# BT_AQ_DOL_R5.net
KiCad netlist of a schematic drawn in EAGLE
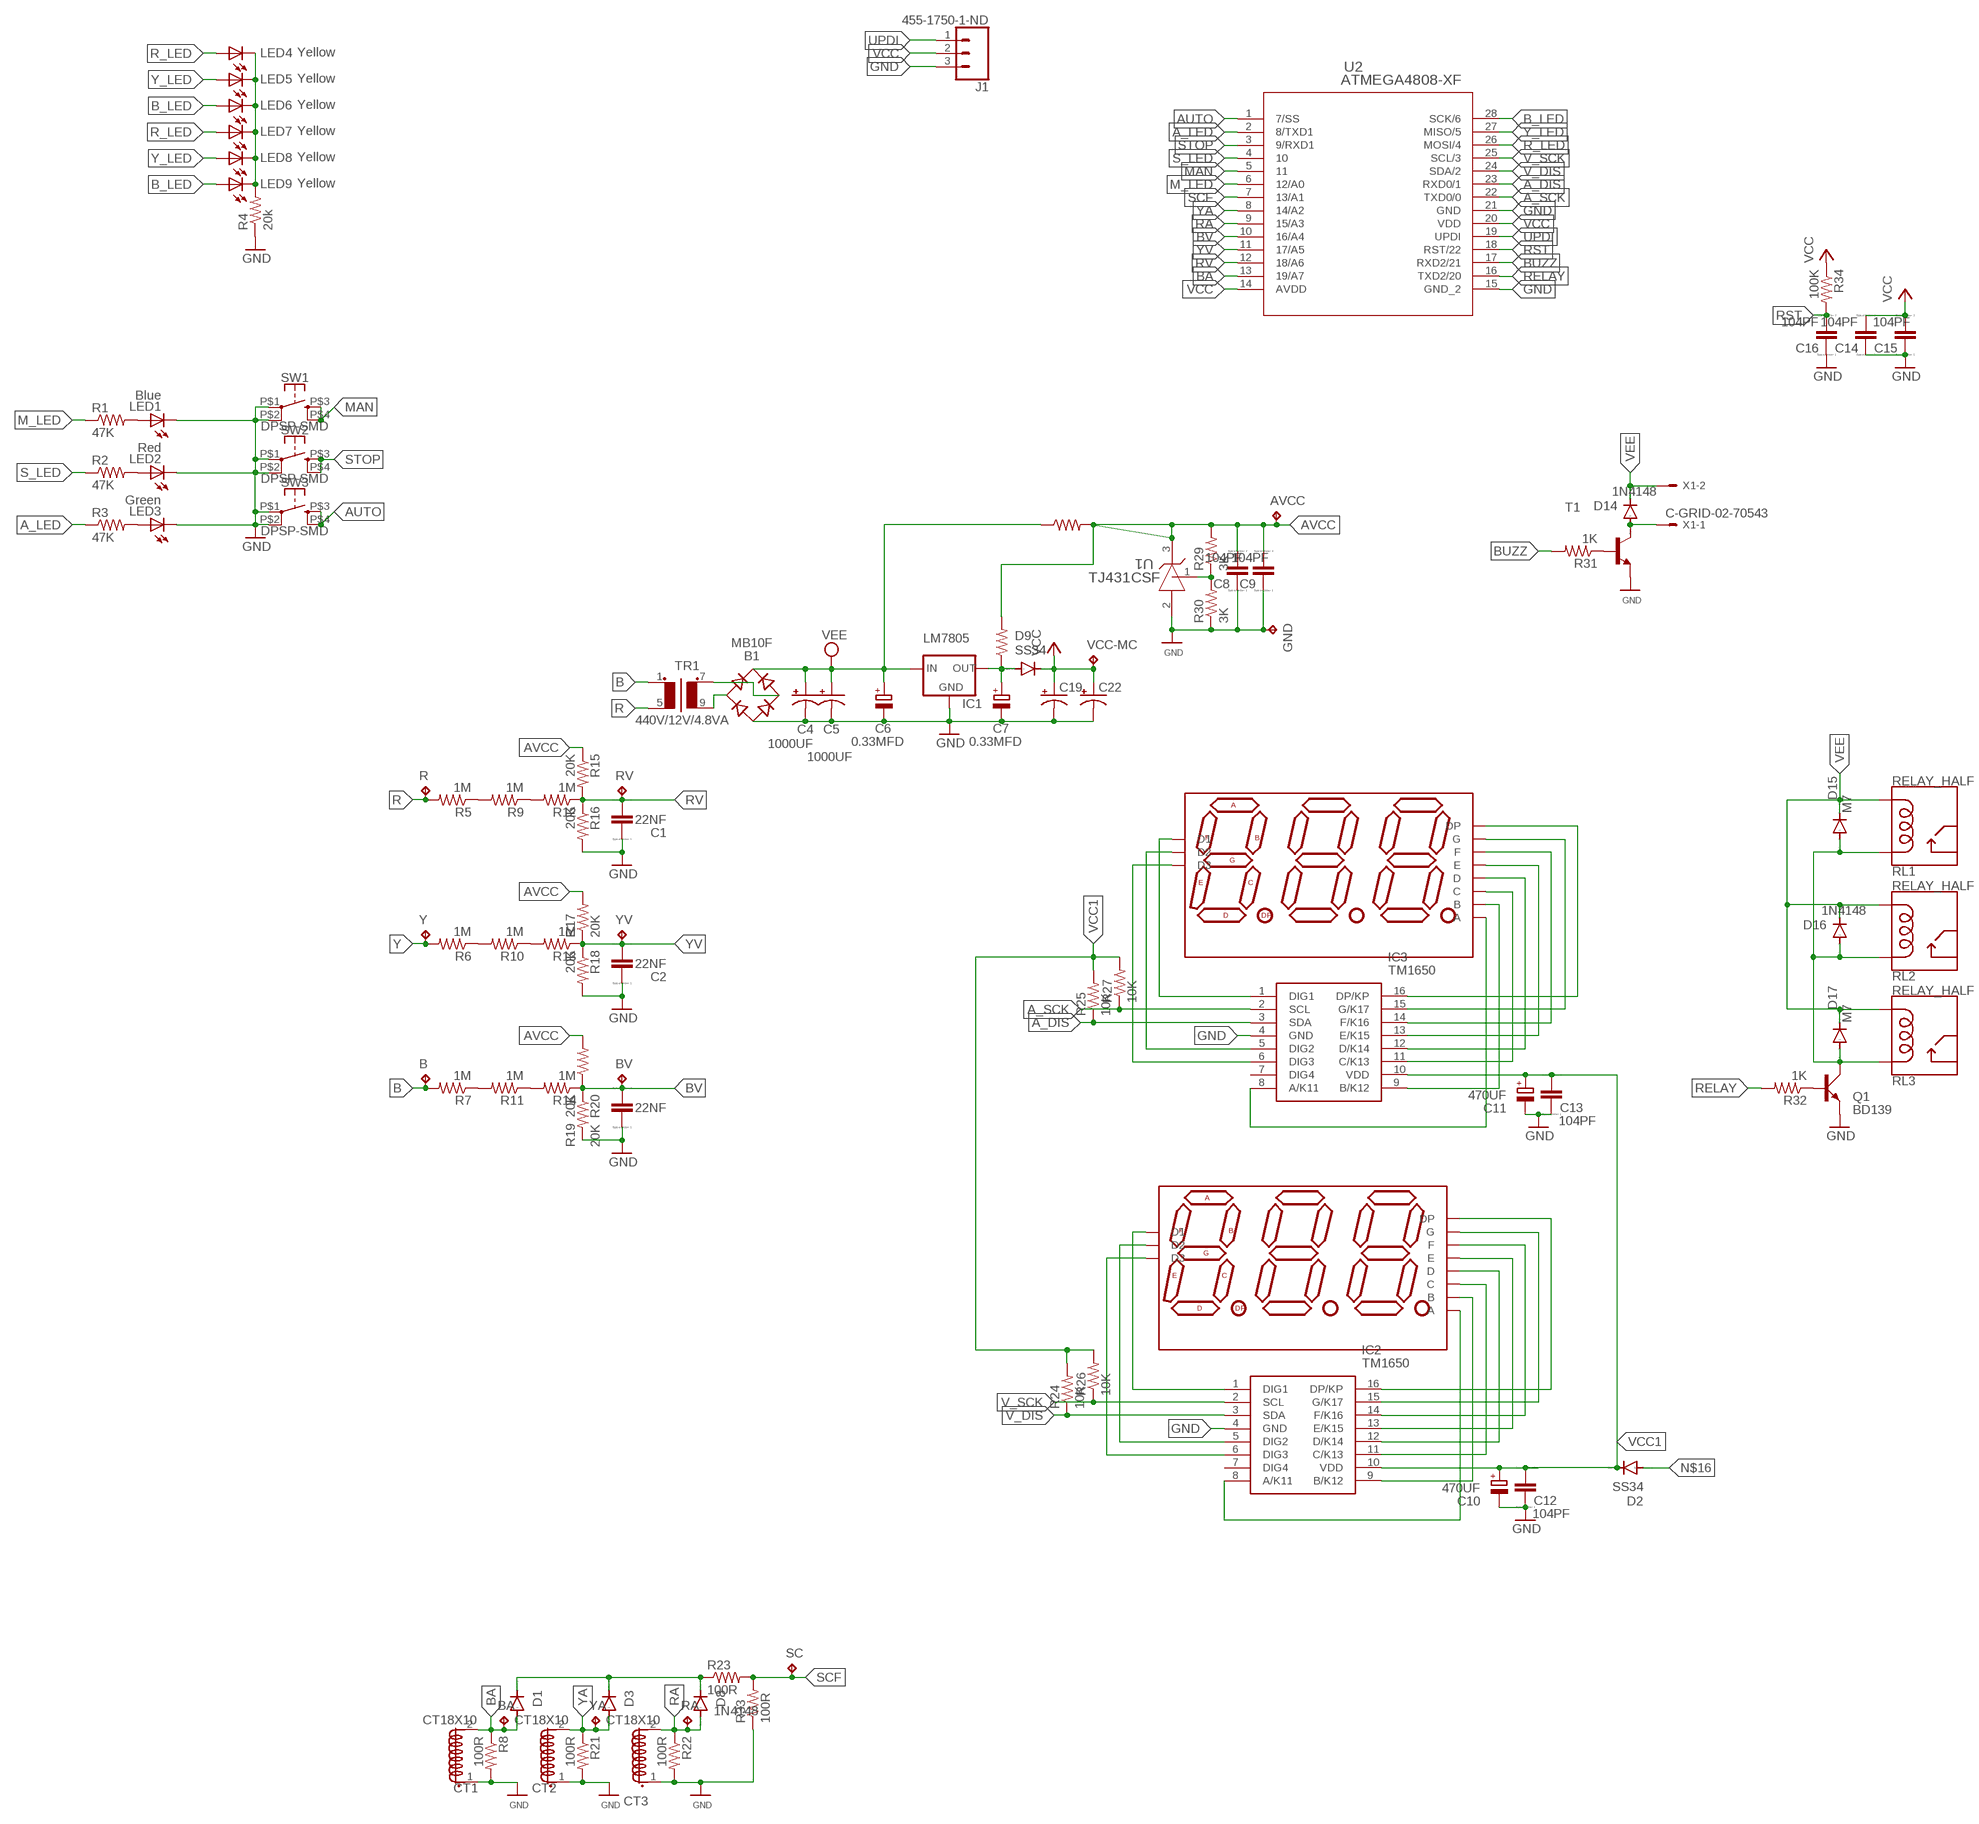
[diagram p0: schematic, sheet 1]

(export (version "E")
  (design (tool "Eeschema 10.0.6"))
  (components
    (comp (ref "AVCC")
      (value "TPB1,27")
      (footprint "eagle-import:B1,27")
      (libsource (lib "eagle-import") (part "TPB1,27"))
    )
    (comp (ref "B")
      (value "TPB1,27")
      (footprint "eagle-import:B1,27")
      (libsource (lib "eagle-import") (part "TPB1,27"))
    )
    (comp (ref "B1")
      (value "MB10F")
      (footprint "eagle-import:SOIC-4")
      (libsource (lib "eagle-import") (part "MBS8"))
    )
    (comp (ref "BA")
      (value "TPB1,27")
      (footprint "eagle-import:B1,27")
      (libsource (lib "eagle-import") (part "TPB1,27"))
    )
    (comp (ref "BV")
      (value "TPB1,27")
      (footprint "eagle-import:B1,27")
      (libsource (lib "eagle-import") (part "TPB1,27"))
    )
    (comp (ref "C1")
      (value "22NF")
      (footprint "eagle-import:C1206")
      (libsource (lib "eagle-import") (part "CC1206"))
    )
    (comp (ref "C2")
      (value "22NF")
      (footprint "eagle-import:C1206")
      (libsource (lib "eagle-import") (part "CC1206"))
    )
    (comp (ref "C3")
      (value "22NF")
      (footprint "eagle-import:C1206")
      (libsource (lib "eagle-import") (part "CC1206"))
    )
    (comp (ref "C4")
      (value "1000UF")
      (footprint "eagle-import:E3,5-10")
      (libsource (lib "eagle-import") (part "CPOL-USE3.5-10"))
    )
    (comp (ref "C5")
      (value "1000UF")
      (footprint "eagle-import:E3,5-10")
      (libsource (lib "eagle-import") (part "CPOL-USE3.5-10"))
    )
    (comp (ref "C6")
      (value "0.33MFD")
      (footprint "eagle-import:E2,5-5")
      (libsource (lib "eagle-import") (part "CPOL-EUE2.5-5"))
    )
    (comp (ref "C7")
      (value "0.33MFD")
      (footprint "eagle-import:E2,5-5")
      (libsource (lib "eagle-import") (part "CPOL-EUE2.5-5"))
    )
    (comp (ref "C8")
      (value "104PF")
      (footprint "eagle-import:C1206")
      (libsource (lib "eagle-import") (part "CC1206"))
    )
    (comp (ref "C9")
      (value "104PF")
      (footprint "eagle-import:C1206")
      (libsource (lib "eagle-import") (part "CC1206"))
    )
    (comp (ref "C10")
      (value "470UF")
      (footprint "eagle-import:E3,5-8")
      (libsource (lib "eagle-import") (part "CPOL-EUE3.5-8"))
    )
    (comp (ref "C11")
      (value "470UF")
      (footprint "eagle-import:E3,5-8")
      (libsource (lib "eagle-import") (part "CPOL-EUE3.5-8"))
    )
    (comp (ref "C12")
      (value "104PF")
      (footprint "eagle-import:C1206")
      (libsource (lib "eagle-import") (part "CC1206"))
    )
    (comp (ref "C13")
      (value "104PF")
      (footprint "eagle-import:C1206")
      (libsource (lib "eagle-import") (part "CC1206"))
    )
    (comp (ref "C14")
      (value "104PF")
      (footprint "eagle-import:C1206")
      (libsource (lib "eagle-import") (part "CC1206"))
    )
    (comp (ref "C15")
      (value "104PF")
      (footprint "eagle-import:C1206")
      (libsource (lib "eagle-import") (part "CC1206"))
    )
    (comp (ref "C16")
      (value "104PF")
      (footprint "eagle-import:C1206")
      (libsource (lib "eagle-import") (part "CC1206"))
    )
    (comp (ref "C19")
      (value "CPOL-USE7.5-18")
      (footprint "eagle-import:E7,5-18")
      (libsource (lib "eagle-import") (part "CPOL-USE7.5-18"))
    )
    (comp (ref "C22")
      (value "CPOL-USE7.5-18")
      (footprint "eagle-import:E7,5-18")
      (libsource (lib "eagle-import") (part "CPOL-USE7.5-18"))
    )
    (comp (ref "CT1")
      (value "CT18X10")
      (footprint "eagle-import:ZMCT103C")
      (libsource (lib "eagle-import") (part "CT18X10"))
    )
    (comp (ref "CT2")
      (value "CT18X10")
      (footprint "eagle-import:ZMCT103C")
      (libsource (lib "eagle-import") (part "CT18X10"))
    )
    (comp (ref "CT3")
      (value "CT18X10")
      (footprint "eagle-import:ZMCT103C")
      (libsource (lib "eagle-import") (part "CT18X10"))
    )
    (comp (ref "D1")
      (value "1N4148")
      (footprint "eagle-import:MINIMELF")
      (libsource (lib "eagle-import") (part "DIODE-MINIMELF"))
    )
    (comp (ref "D2")
      (value "SS34")
      (footprint "eagle-import:DO-214AC")
      (libsource (lib "eagle-import") (part "DIODE-DO-214AC"))
    )
    (comp (ref "D3")
      (value "1N4148")
      (footprint "eagle-import:MINIMELF")
      (libsource (lib "eagle-import") (part "DIODE-MINIMELF"))
    )
    (comp (ref "D8")
      (value "1N4148")
      (footprint "eagle-import:MINIMELF")
      (libsource (lib "eagle-import") (part "DIODE-MINIMELF"))
    )
    (comp (ref "D9")
      (value "SS34")
      (footprint "eagle-import:DO-214AC")
      (libsource (lib "eagle-import") (part "DIODE-DO-214AC"))
    )
    (comp (ref "D12")
      (value "SUNR036CC3D")
      (footprint "eagle-import:7S3D036_DIP")
      (libsource (lib "eagle-import") (part "7SEGMENT-3DIGITDIP"))
    )
    (comp (ref "D13")
      (value "SUNR036CC3D")
      (footprint "eagle-import:7S3D036_DIP")
      (libsource (lib "eagle-import") (part "7SEGMENT-3DIGITDIP"))
    )
    (comp (ref "D14")
      (value "1N4148")
      (footprint "eagle-import:MINIMELF")
      (libsource (lib "eagle-import") (part "DIODE-MINIMELF"))
    )
    (comp (ref "D15")
      (value "M7")
      (footprint "eagle-import:DO-214AC")
      (libsource (lib "eagle-import") (part "DIODE-DO-214AC"))
    )
    (comp (ref "D16")
      (value "1N4148")
      (footprint "eagle-import:MINIMELF")
      (libsource (lib "eagle-import") (part "DIODE-MINIMELF"))
    )
    (comp (ref "D17")
      (value "M7")
      (footprint "eagle-import:DO-214AC")
      (libsource (lib "eagle-import") (part "DIODE-DO-214AC"))
    )
    (comp (ref "GND")
      (value "TPB1,27")
      (footprint "eagle-import:B1,27")
      (libsource (lib "eagle-import") (part "TPB1,27"))
    )
    (comp (ref "IC1")
      (value "LM7805")
      (footprint "eagle-import:78XXS")
      (libsource (lib "eagle-import") (part "78XXS"))
    )
    (comp (ref "IC2")
      (value "TM1650")
      (footprint "eagle-import:SOIC127P604X185-16N")
      (fields (field (name "MANUFACTURER_PART_NUMBER") "tm1650"))
      (libsource (lib "eagle-import") (part "TM1650"))
    )
    (comp (ref "IC3")
      (value "TM1650")
      (footprint "eagle-import:SOIC127P604X185-16N")
      (fields (field (name "MANUFACTURER_PART_NUMBER") "tm1650"))
      (libsource (lib "eagle-import") (part "TM1650"))
    )
    (comp (ref "J1")
      (value "455-1750-1-ND")
      (footprint "eagle-import:1X03")
      (libsource (lib "eagle-import") (part "CONN_03"))
    )
    (comp (ref "LED1")
      (value "Blue")
      (footprint "eagle-import:LED3MM")
      (libsource (lib "eagle-import") (part "LED3MM"))
    )
    (comp (ref "LED2")
      (value "Red")
      (footprint "eagle-import:LED3MM")
      (libsource (lib "eagle-import") (part "LED3MM"))
    )
    (comp (ref "LED3")
      (value "Green")
      (footprint "eagle-import:LED3MM")
      (libsource (lib "eagle-import") (part "LED3MM"))
    )
    (comp (ref "LED4")
      (value "Yellow")
      (footprint "eagle-import:LED3MM")
      (libsource (lib "eagle-import") (part "LED3MM"))
    )
    (comp (ref "LED5")
      (value "Yellow")
      (footprint "eagle-import:LED3MM")
      (libsource (lib "eagle-import") (part "LED3MM"))
    )
    (comp (ref "LED6")
      (value "Yellow")
      (footprint "eagle-import:LED3MM")
      (libsource (lib "eagle-import") (part "LED3MM"))
    )
    (comp (ref "LED7")
      (value "Yellow")
      (footprint "eagle-import:LED3MM")
      (libsource (lib "eagle-import") (part "LED3MM"))
    )
    (comp (ref "LED8")
      (value "Yellow")
      (footprint "eagle-import:LED3MM")
      (libsource (lib "eagle-import") (part "LED3MM"))
    )
    (comp (ref "LED9")
      (value "Yellow")
      (footprint "eagle-import:LED3MM")
      (libsource (lib "eagle-import") (part "LED3MM"))
    )
    (comp (ref "Q1")
      (value "BD139")
      (footprint "eagle-import:TO126AV")
      (libsource (lib "eagle-import") (part "BD139"))
    )
    (comp (ref "R")
      (value "TPB1,27")
      (footprint "eagle-import:B1,27")
      (libsource (lib "eagle-import") (part "TPB1,27"))
    )
    (comp (ref "R1")
      (value "47K")
      (footprint "eagle-import:M1206")
      (libsource (lib "eagle-import") (part "rcl_334_R-US_M1206"))
    )
    (comp (ref "R2")
      (value "47K")
      (footprint "eagle-import:M1206")
      (libsource (lib "eagle-import") (part "rcl_334_R-US_M1206"))
    )
    (comp (ref "R3")
      (value "47K")
      (footprint "eagle-import:M1206")
      (libsource (lib "eagle-import") (part "rcl_334_R-US_M1206"))
    )
    (comp (ref "R4")
      (value "20k")
      (footprint "eagle-import:M1206")
      (libsource (lib "eagle-import") (part "rcl_334_R-US_M1206"))
    )
    (comp (ref "R5")
      (value "1M")
      (footprint "eagle-import:M1206")
      (libsource (lib "eagle-import") (part "rcl_334_R-US_M1206"))
    )
    (comp (ref "R6")
      (value "1M")
      (footprint "eagle-import:M1206")
      (libsource (lib "eagle-import") (part "rcl_334_R-US_M1206"))
    )
    (comp (ref "R7")
      (value "1M")
      (footprint "eagle-import:M1206")
      (libsource (lib "eagle-import") (part "rcl_334_R-US_M1206"))
    )
    (comp (ref "R8")
      (value "100R")
      (footprint "eagle-import:M1206")
      (libsource (lib "eagle-import") (part "R-US_M1206"))
    )
    (comp (ref "R9")
      (value "1M")
      (footprint "eagle-import:M1206")
      (libsource (lib "eagle-import") (part "rcl_334_R-US_M1206"))
    )
    (comp (ref "R10")
      (value "1M")
      (footprint "eagle-import:M1206")
      (libsource (lib "eagle-import") (part "rcl_334_R-US_M1206"))
    )
    (comp (ref "R11")
      (value "1M")
      (footprint "eagle-import:M1206")
      (libsource (lib "eagle-import") (part "rcl_334_R-US_M1206"))
    )
    (comp (ref "R12")
      (value "1M")
      (footprint "eagle-import:M1206")
      (libsource (lib "eagle-import") (part "rcl_334_R-US_M1206"))
    )
    (comp (ref "R13")
      (value "1M")
      (footprint "eagle-import:M1206")
      (libsource (lib "eagle-import") (part "rcl_334_R-US_M1206"))
    )
    (comp (ref "R14")
      (value "1M")
      (footprint "eagle-import:M1206")
      (libsource (lib "eagle-import") (part "rcl_334_R-US_M1206"))
    )
    (comp (ref "R15")
      (value "20K")
      (footprint "eagle-import:M1206")
      (libsource (lib "eagle-import") (part "rcl_334_R-US_M1206"))
    )
    (comp (ref "R16")
      (value "20K")
      (footprint "eagle-import:M1206")
      (libsource (lib "eagle-import") (part "rcl_334_R-US_M1206"))
    )
    (comp (ref "R17")
      (value "20K")
      (footprint "eagle-import:M1206")
      (libsource (lib "eagle-import") (part "rcl_334_R-US_M1206"))
    )
    (comp (ref "R18")
      (value "20K")
      (footprint "eagle-import:M1206")
      (libsource (lib "eagle-import") (part "rcl_334_R-US_M1206"))
    )
    (comp (ref "R19")
      (value "20K")
      (footprint "eagle-import:M1206")
      (libsource (lib "eagle-import") (part "rcl_334_R-US_M1206"))
    )
    (comp (ref "R20")
      (value "20K")
      (footprint "eagle-import:M1206")
      (libsource (lib "eagle-import") (part "rcl_334_R-US_M1206"))
    )
    (comp (ref "R21")
      (value "100R")
      (footprint "eagle-import:M1206")
      (libsource (lib "eagle-import") (part "R-US_M1206"))
    )
    (comp (ref "R22")
      (value "100R")
      (footprint "eagle-import:M1206")
      (libsource (lib "eagle-import") (part "R-US_M1206"))
    )
    (comp (ref "R23")
      (value "100R")
      (footprint "eagle-import:M1206")
      (libsource (lib "eagle-import") (part "R-US_M1206"))
    )
    (comp (ref "R24")
      (value "10K")
      (footprint "eagle-import:M1206")
      (libsource (lib "eagle-import") (part "rcl_334_R-US_M1206"))
    )
    (comp (ref "R25")
      (value "10K")
      (footprint "eagle-import:M1206")
      (libsource (lib "eagle-import") (part "rcl_334_R-US_M1206"))
    )
    (comp (ref "R26")
      (value "10K")
      (footprint "eagle-import:M1206")
      (libsource (lib "eagle-import") (part "rcl_334_R-US_M1206"))
    )
    (comp (ref "R27")
      (value "10K")
      (footprint "eagle-import:M1206")
      (libsource (lib "eagle-import") (part "rcl_334_R-US_M1206"))
    )
    (comp (ref "R28")
      (value "10K")
      (footprint "eagle-import:M1206")
      (libsource (lib "eagle-import") (part "R-US_M1206"))
    )
    (comp (ref "R29")
      (value "3K")
      (footprint "eagle-import:M1206")
      (libsource (lib "eagle-import") (part "R-US_M1206"))
    )
    (comp (ref "R30")
      (value "3K")
      (footprint "eagle-import:M1206")
      (libsource (lib "eagle-import") (part "R-US_M1206"))
    )
    (comp (ref "R31")
      (value "1K")
      (footprint "eagle-import:M1206")
      (libsource (lib "eagle-import") (part "rcl_334_R-US_M1206"))
    )
    (comp (ref "R32")
      (value "1K")
      (footprint "eagle-import:M1206")
      (libsource (lib "eagle-import") (part "rcl_334_R-US_M1206"))
    )
    (comp (ref "R33")
      (value "100R")
      (footprint "eagle-import:M1206")
      (libsource (lib "eagle-import") (part "R-US_M1206"))
    )
    (comp (ref "R34")
      (value "100K")
      (footprint "eagle-import:M1206")
      (libsource (lib "eagle-import") (part "rcl_334_R-US_M1206"))
    )
    (comp (ref "R35")
      (value "10K")
      (footprint "eagle-import:M1206")
      (libsource (lib "eagle-import") (part "R-US_M1206"))
    )
    (comp (ref "RA")
      (value "TPB1,27")
      (footprint "eagle-import:B1,27")
      (libsource (lib "eagle-import") (part "TPB1,27"))
    )
    (comp (ref "RL1")
      (value "RELAY_HALF")
      (footprint "eagle-import:DT90_HALF")
      (libsource (lib "eagle-import") (part "RELAY_HALF"))
    )
    (comp (ref "RL2")
      (value "RELAY_HALF")
      (footprint "eagle-import:DT90_HALF")
      (libsource (lib "eagle-import") (part "RELAY_HALF"))
    )
    (comp (ref "RL3")
      (value "RELAY_HALF")
      (footprint "eagle-import:DT90_HALF")
      (libsource (lib "eagle-import") (part "RELAY_HALF"))
    )
    (comp (ref "RV")
      (value "TPB1,27")
      (footprint "eagle-import:B1,27")
      (libsource (lib "eagle-import") (part "TPB1,27"))
    )
    (comp (ref "SC")
      (value "TPB1,27")
      (footprint "eagle-import:B1,27")
      (libsource (lib "eagle-import") (part "TPB1,27"))
    )
    (comp (ref "SW1")
      (value "DPSP-SMD")
      (footprint "eagle-import:B3F-40XX-ROUND-SMD")
      (libsource (lib "eagle-import") (part "DPSP-SMD"))
    )
    (comp (ref "SW2")
      (value "DPSP-SMD")
      (footprint "eagle-import:B3F-40XX-ROUND-SMD")
      (libsource (lib "eagle-import") (part "DPSP-SMD"))
    )
    (comp (ref "SW3")
      (value "DPSP-SMD")
      (footprint "eagle-import:B3F-40XX-ROUND-SMD")
      (libsource (lib "eagle-import") (part "DPSP-SMD"))
    )
    (comp (ref "T1")
      (value "MMUN2213LT1-NPN-SC59-BEC")
      (footprint "eagle-import:SC59-BEC")
      (libsource (lib "eagle-import") (part "-NPN-SC59-BECMMUN2213LT1"))
    )
    (comp (ref "TR1")
      (value "440V/12V/4.8VA")
      (footprint "eagle-import:440V12V6VA")
      (libsource (lib "eagle-import") (part "TRANSFORMER6VA"))
    )
    (comp (ref "U1")
      (value "TJ431CSF")
      (footprint "eagle-import:SOT-23")
      (fields
        (field (name "MANUFACTURER_PART_NUMBER") "TL431IDBZTG4")
        (field (name "COPYRIGHT") "Copyright (C) 2022 Ultra Librarian. All rights reserved.")
      )
      (libsource (lib "eagle-import") (part "TJ431CSFDBZ0003A_L"))
    )
    (comp (ref "U2")
      (value "ATMEGA4808-XF")
      (footprint "eagle-import:SSOP28_SS_MCH")
      (fields (field (name "COPYRIGHT") "Copyright (C) 2022 Ultra Librarian. All rights reserved."))
      (libsource (lib "eagle-import") (part "ATMEGA4808-XF"))
    )
    (comp (ref "VCC-MC")
      (value "TPB1,27")
      (footprint "eagle-import:B1,27")
      (libsource (lib "eagle-import") (part "TPB1,27"))
    )
    (comp (ref "X1")
      (value "C-GRID-02-70543")
      (footprint "eagle-import:70543-02")
      (fields (field (name "MF") "MOLEX"))
      (libsource (lib "eagle-import") (part "C-GRID-02-70543"))
    )
    (comp (ref "Y")
      (value "TPB1,27")
      (footprint "eagle-import:B1,27")
      (libsource (lib "eagle-import") (part "TPB1,27"))
    )
    (comp (ref "YA")
      (value "TPB1,27")
      (footprint "eagle-import:B1,27")
      (libsource (lib "eagle-import") (part "TPB1,27"))
    )
    (comp (ref "YV")
      (value "TPB1,27")
      (footprint "eagle-import:B1,27")
      (libsource (lib "eagle-import") (part "TPB1,27"))
    )
  )
  (nets
    (net (code "1") (name "AUTO") (class "Default")
      (node (ref "SW3") (pin "P$3") (pinfunction "3_P$3") (pintype "passive"))
      (node (ref "SW3") (pin "P$4") (pinfunction "4_P$4") (pintype "passive"))
      (node (ref "U2") (pin "1") (pinfunction "7/SS_1") (pintype "bidirectional"))
    )
    (net (code "2") (name "AVCC") (class "Default")
      (node (ref "AVCC") (pin "TP") (pinfunction "TP_TP") (pintype "input"))
      (node (ref "C8") (pin "2") (pinfunction "2_2") (pintype "passive"))
      (node (ref "C9") (pin "2") (pinfunction "2_2") (pintype "passive"))
      (node (ref "R15") (pin "1") (pinfunction "1_1") (pintype "passive"))
      (node (ref "R17") (pin "2") (pinfunction "2_2") (pintype "passive"))
      (node (ref "R19") (pin "2") (pinfunction "2_2") (pintype "passive"))
      (node (ref "R28") (pin "2") (pinfunction "2_2") (pintype "passive"))
      (node (ref "R29") (pin "2") (pinfunction "2_2") (pintype "passive"))
      (node (ref "R35") (pin "2") (pinfunction "2_2") (pintype "passive"))
      (node (ref "U1") (pin "3") (pinfunction "CATHODE_3") (pintype "passive"))
    )
    (net (code "3") (name "A_DIS") (class "Default")
      (node (ref "IC3") (pin "3") (pinfunction "SDA_3") (pintype "input"))
      (node (ref "R25") (pin "1") (pinfunction "1_1") (pintype "passive"))
      (node (ref "U2") (pin "23") (pinfunction "RXD0/1_23") (pintype "bidirectional"))
    )
    (net (code "4") (name "A_LED") (class "Default")
      (node (ref "R3") (pin "1") (pinfunction "1_1") (pintype "passive"))
      (node (ref "U2") (pin "2") (pinfunction "8/TXD1_2") (pintype "bidirectional"))
    )
    (net (code "5") (name "A_SCK") (class "Default")
      (node (ref "IC3") (pin "2") (pinfunction "SCL_2") (pintype "input"))
      (node (ref "R27") (pin "1") (pinfunction "1_1") (pintype "passive"))
      (node (ref "U2") (pin "22") (pinfunction "TXD0/0_22") (pintype "bidirectional"))
    )
    (net (code "6") (name "B") (class "Default")
      (node (ref "B") (pin "TP") (pinfunction "TP_TP") (pintype "input"))
      (node (ref "R7") (pin "2") (pinfunction "2_2") (pintype "passive"))
      (node (ref "TR1") (pin "1") (pinfunction "P1_1") (pintype "passive"))
    )
    (net (code "7") (name "BA") (class "Default")
      (node (ref "BA") (pin "TP") (pinfunction "TP_TP") (pintype "input"))
      (node (ref "CT1") (pin "2") (pinfunction "S1.2_2") (pintype "passive"))
      (node (ref "D1") (pin "A") (pinfunction "A_A") (pintype "passive"))
      (node (ref "R8") (pin "1") (pinfunction "1_1") (pintype "passive"))
      (node (ref "U2") (pin "13") (pinfunction "19/A7_13") (pintype "bidirectional"))
    )
    (net (code "8") (name "BUZZ") (class "Default")
      (node (ref "R31") (pin "2") (pinfunction "2_2") (pintype "passive"))
      (node (ref "U2") (pin "17") (pinfunction "RXD2/21_17") (pintype "bidirectional"))
    )
    (net (code "9") (name "BV") (class "Default")
      (node (ref "BV") (pin "TP") (pinfunction "TP_TP") (pintype "input"))
      (node (ref "C3") (pin "2") (pinfunction "2_2") (pintype "passive"))
      (node (ref "R14") (pin "1") (pinfunction "1_1") (pintype "passive"))
      (node (ref "R19") (pin "1") (pinfunction "1_1") (pintype "passive"))
      (node (ref "R20") (pin "1") (pinfunction "1_1") (pintype "passive"))
      (node (ref "U2") (pin "10") (pinfunction "16/A4_10") (pintype "bidirectional"))
    )
    (net (code "10") (name "B_LED") (class "Default")
      (node (ref "LED6") (pin "A") (pinfunction "A_A") (pintype "passive"))
      (node (ref "LED9") (pin "A") (pinfunction "A_A") (pintype "passive"))
      (node (ref "U2") (pin "28") (pinfunction "SCK/6_28") (pintype "bidirectional"))
    )
    (net (code "11") (name "GND") (class "Default")
      (node (ref "B1") (pin "-") (pinfunction "-_-") (pintype "passive"))
      (node (ref "C1") (pin "1") (pinfunction "1_1") (pintype "passive"))
      (node (ref "C10") (pin "-") (pinfunction "-_-") (pintype "passive"))
      (node (ref "C11") (pin "-") (pinfunction "-_-") (pintype "passive"))
      (node (ref "C12") (pin "1") (pinfunction "1_1") (pintype "passive"))
      (node (ref "C13") (pin "1") (pinfunction "1_1") (pintype "passive"))
      (node (ref "C14") (pin "1") (pinfunction "1_1") (pintype "passive"))
      (node (ref "C15") (pin "1") (pinfunction "1_1") (pintype "passive"))
      (node (ref "C16") (pin "1") (pinfunction "1_1") (pintype "passive"))
      (node (ref "C19") (pin "-") (pinfunction "-_-") (pintype "passive"))
      (node (ref "C2") (pin "1") (pinfunction "1_1") (pintype "passive"))
      (node (ref "C22") (pin "-") (pinfunction "-_-") (pintype "passive"))
      (node (ref "C3") (pin "1") (pinfunction "1_1") (pintype "passive"))
      (node (ref "C4") (pin "-") (pinfunction "-_-") (pintype "passive"))
      (node (ref "C5") (pin "-") (pinfunction "-_-") (pintype "passive"))
      (node (ref "C6") (pin "-") (pinfunction "-_-") (pintype "passive"))
      (node (ref "C7") (pin "-") (pinfunction "-_-") (pintype "passive"))
      (node (ref "C8") (pin "1") (pinfunction "1_1") (pintype "passive"))
      (node (ref "C9") (pin "1") (pinfunction "1_1") (pintype "passive"))
      (node (ref "CT1") (pin "1") (pinfunction "S1.1_1") (pintype "passive"))
      (node (ref "CT2") (pin "1") (pinfunction "S1.1_1") (pintype "passive"))
      (node (ref "CT3") (pin "1") (pinfunction "S1.1_1") (pintype "passive"))
      (node (ref "GND") (pin "TP") (pinfunction "TP_TP") (pintype "input"))
      (node (ref "IC1") (pin "GND") (pinfunction "GND_GND") (pintype "input"))
      (node (ref "IC2") (pin "4") (pinfunction "GND_4") (pintype "power_in"))
      (node (ref "IC3") (pin "4") (pinfunction "GND_4") (pintype "power_in"))
      (node (ref "J1") (pin "3") (pinfunction "3_3") (pintype "passive"))
      (node (ref "LED1") (pin "K") (pinfunction "C_K") (pintype "passive"))
      (node (ref "LED2") (pin "K") (pinfunction "C_K") (pintype "passive"))
      (node (ref "LED3") (pin "K") (pinfunction "C_K") (pintype "passive"))
      (node (ref "Q1") (pin "E") (pinfunction "E_E") (pintype "passive"))
      (node (ref "R16") (pin "2") (pinfunction "2_2") (pintype "passive"))
      (node (ref "R18") (pin "2") (pinfunction "2_2") (pintype "passive"))
      (node (ref "R20") (pin "2") (pinfunction "2_2") (pintype "passive"))
      (node (ref "R21") (pin "2") (pinfunction "2_2") (pintype "passive"))
      (node (ref "R22") (pin "2") (pinfunction "2_2") (pintype "passive"))
      (node (ref "R30") (pin "1") (pinfunction "1_1") (pintype "passive"))
      (node (ref "R33") (pin "1") (pinfunction "1_1") (pintype "passive"))
      (node (ref "R4") (pin "1") (pinfunction "1_1") (pintype "passive"))
      (node (ref "R8") (pin "2") (pinfunction "2_2") (pintype "passive"))
      (node (ref "SW1") (pin "P$1") (pinfunction "1_P$1") (pintype "passive"))
      (node (ref "SW1") (pin "P$2") (pinfunction "2_P$2") (pintype "passive"))
      (node (ref "SW2") (pin "P$1") (pinfunction "1_P$1") (pintype "passive"))
      (node (ref "SW2") (pin "P$2") (pinfunction "2_P$2") (pintype "passive"))
      (node (ref "SW3") (pin "P$1") (pinfunction "1_P$1") (pintype "passive"))
      (node (ref "SW3") (pin "P$2") (pinfunction "2_P$2") (pintype "passive"))
      (node (ref "T1") (pin "E") (pinfunction "E_E") (pintype "passive"))
      (node (ref "U1") (pin "2") (pinfunction "ANODE_2") (pintype "passive"))
      (node (ref "U2") (pin "15") (pinfunction "GND_2_15") (pintype "passive"))
      (node (ref "U2") (pin "21") (pinfunction "GND_21") (pintype "passive"))
    )
    (net (code "12") (name "MAN") (class "Default")
      (node (ref "SW1") (pin "P$3") (pinfunction "3_P$3") (pintype "passive"))
      (node (ref "SW1") (pin "P$4") (pinfunction "4_P$4") (pintype "passive"))
      (node (ref "U2") (pin "5") (pinfunction "11_5") (pintype "bidirectional"))
    )
    (net (code "13") (name "M_LED") (class "Default")
      (node (ref "R1") (pin "1") (pinfunction "1_1") (pintype "passive"))
      (node (ref "U2") (pin "6") (pinfunction "12/A0_6") (pintype "bidirectional"))
    )
    (net (code "14") (name "N$16") (class "Default")
      (node (ref "C7") (pin "+") (pinfunction "+_+") (pintype "passive"))
      (node (ref "D2") (pin "A") (pinfunction "A_A") (pintype "passive"))
      (node (ref "D9") (pin "A") (pinfunction "A_A") (pintype "passive"))
      (node (ref "IC1") (pin "OUT") (pinfunction "OUT_OUT") (pintype "passive"))
      (node (ref "R35") (pin "1") (pinfunction "1_1") (pintype "passive"))
    )
    (net (code "15") (name "Net-(B1-AC1)") (class "Default")
      (node (ref "B1") (pin "~1") (pinfunction "AC1_~1") (pintype "passive"))
      (node (ref "TR1") (pin "9") (pinfunction "S2_9") (pintype "passive"))
    )
    (net (code "16") (name "Net-(B1-AC2)") (class "Default")
      (node (ref "B1") (pin "~2") (pinfunction "AC2_~2") (pintype "passive"))
      (node (ref "TR1") (pin "7") (pinfunction "S1_7") (pintype "passive"))
    )
    (net (code "17") (name "Net-(D1-PadC)") (class "Default")
      (node (ref "D1") (pin "C") (pinfunction "C_C") (pintype "passive"))
      (node (ref "D3") (pin "C") (pinfunction "C_C") (pintype "passive"))
      (node (ref "D8") (pin "C") (pinfunction "C_C") (pintype "passive"))
      (node (ref "R23") (pin "1") (pinfunction "1_1") (pintype "passive"))
    )
    (net (code "18") (name "Net-(D12-A)") (class "Default")
      (node (ref "D12") (pin "11") (pinfunction "A_11") (pintype "bidirectional"))
      (node (ref "IC2") (pin "8") (pinfunction "A/K11_8") (pintype "bidirectional"))
    )
    (net (code "19") (name "Net-(D12-B)") (class "Default")
      (node (ref "D12") (pin "7") (pinfunction "B_7") (pintype "bidirectional"))
      (node (ref "IC2") (pin "9") (pinfunction "B/K12_9") (pintype "bidirectional"))
    )
    (net (code "20") (name "Net-(D12-C)") (class "Default")
      (node (ref "D12") (pin "4") (pinfunction "C_4") (pintype "bidirectional"))
      (node (ref "IC2") (pin "11") (pinfunction "C/K13_11") (pintype "bidirectional"))
    )
    (net (code "21") (name "Net-(D12-D)") (class "Default")
      (node (ref "D12") (pin "2") (pinfunction "D_2") (pintype "bidirectional"))
      (node (ref "IC2") (pin "12") (pinfunction "D/K14_12") (pintype "bidirectional"))
    )
    (net (code "22") (name "Net-(D12-D1)") (class "Default")
      (node (ref "D12") (pin "12") (pinfunction "D1_12") (pintype "bidirectional"))
      (node (ref "IC2") (pin "1") (pinfunction "DIG1_1") (pintype "bidirectional"))
    )
    (net (code "23") (name "Net-(D12-D2)") (class "Default")
      (node (ref "D12") (pin "9") (pinfunction "D2_9") (pintype "bidirectional"))
      (node (ref "IC2") (pin "5") (pinfunction "DIG2_5") (pintype "bidirectional"))
    )
    (net (code "24") (name "Net-(D12-D3)") (class "Default")
      (node (ref "D12") (pin "8") (pinfunction "D3_8") (pintype "bidirectional"))
      (node (ref "IC2") (pin "6") (pinfunction "DIG3_6") (pintype "bidirectional"))
    )
    (net (code "25") (name "Net-(D12-DP)") (class "Default")
      (node (ref "D12") (pin "3") (pinfunction "DP_3") (pintype "bidirectional"))
      (node (ref "IC2") (pin "16") (pinfunction "DP/KP_16") (pintype "bidirectional"))
    )
    (net (code "26") (name "Net-(D12-E)") (class "Default")
      (node (ref "D12") (pin "1") (pinfunction "E_1") (pintype "bidirectional"))
      (node (ref "IC2") (pin "13") (pinfunction "E/K15_13") (pintype "bidirectional"))
    )
    (net (code "27") (name "Net-(D12-F)") (class "Default")
      (node (ref "D12") (pin "10") (pinfunction "F_10") (pintype "bidirectional"))
      (node (ref "IC2") (pin "14") (pinfunction "F/K16_14") (pintype "bidirectional"))
    )
    (net (code "28") (name "Net-(D12-G)") (class "Default")
      (node (ref "D12") (pin "5") (pinfunction "G_5") (pintype "bidirectional"))
      (node (ref "IC2") (pin "15") (pinfunction "G/K17_15") (pintype "bidirectional"))
    )
    (net (code "29") (name "Net-(D13-A)") (class "Default")
      (node (ref "D13") (pin "11") (pinfunction "A_11") (pintype "bidirectional"))
      (node (ref "IC3") (pin "8") (pinfunction "A/K11_8") (pintype "bidirectional"))
    )
    (net (code "30") (name "Net-(D13-B)") (class "Default")
      (node (ref "D13") (pin "7") (pinfunction "B_7") (pintype "bidirectional"))
      (node (ref "IC3") (pin "9") (pinfunction "B/K12_9") (pintype "bidirectional"))
    )
    (net (code "31") (name "Net-(D13-C)") (class "Default")
      (node (ref "D13") (pin "4") (pinfunction "C_4") (pintype "bidirectional"))
      (node (ref "IC3") (pin "11") (pinfunction "C/K13_11") (pintype "bidirectional"))
    )
    (net (code "32") (name "Net-(D13-D)") (class "Default")
      (node (ref "D13") (pin "2") (pinfunction "D_2") (pintype "bidirectional"))
      (node (ref "IC3") (pin "12") (pinfunction "D/K14_12") (pintype "bidirectional"))
    )
    (net (code "33") (name "Net-(D13-D1)") (class "Default")
      (node (ref "D13") (pin "12") (pinfunction "D1_12") (pintype "bidirectional"))
      (node (ref "IC3") (pin "1") (pinfunction "DIG1_1") (pintype "bidirectional"))
    )
    (net (code "34") (name "Net-(D13-D2)") (class "Default")
      (node (ref "D13") (pin "9") (pinfunction "D2_9") (pintype "bidirectional"))
      (node (ref "IC3") (pin "5") (pinfunction "DIG2_5") (pintype "bidirectional"))
    )
    (net (code "35") (name "Net-(D13-D3)") (class "Default")
      (node (ref "D13") (pin "8") (pinfunction "D3_8") (pintype "bidirectional"))
      (node (ref "IC3") (pin "6") (pinfunction "DIG3_6") (pintype "bidirectional"))
    )
    (net (code "36") (name "Net-(D13-DP)") (class "Default")
      (node (ref "D13") (pin "3") (pinfunction "DP_3") (pintype "bidirectional"))
      (node (ref "IC3") (pin "16") (pinfunction "DP/KP_16") (pintype "bidirectional"))
    )
    (net (code "37") (name "Net-(D13-E)") (class "Default")
      (node (ref "D13") (pin "1") (pinfunction "E_1") (pintype "bidirectional"))
      (node (ref "IC3") (pin "13") (pinfunction "E/K15_13") (pintype "bidirectional"))
    )
    (net (code "38") (name "Net-(D13-F)") (class "Default")
      (node (ref "D13") (pin "10") (pinfunction "F_10") (pintype "bidirectional"))
      (node (ref "IC3") (pin "14") (pinfunction "F/K16_14") (pintype "bidirectional"))
    )
    (net (code "39") (name "Net-(D13-G)") (class "Default")
      (node (ref "D13") (pin "5") (pinfunction "G_5") (pintype "bidirectional"))
      (node (ref "IC3") (pin "15") (pinfunction "G/K17_15") (pintype "bidirectional"))
    )
    (net (code "40") (name "Net-(LED1-PadA)") (class "Default")
      (node (ref "LED1") (pin "A") (pinfunction "A_A") (pintype "passive"))
      (node (ref "R1") (pin "2") (pinfunction "2_2") (pintype "passive"))
    )
    (net (code "41") (name "Net-(LED2-PadA)") (class "Default")
      (node (ref "LED2") (pin "A") (pinfunction "A_A") (pintype "passive"))
      (node (ref "R2") (pin "2") (pinfunction "2_2") (pintype "passive"))
    )
    (net (code "42") (name "Net-(LED3-PadA)") (class "Default")
      (node (ref "LED3") (pin "A") (pinfunction "A_A") (pintype "passive"))
      (node (ref "R3") (pin "2") (pinfunction "2_2") (pintype "passive"))
    )
    (net (code "43") (name "Net-(LED4-C)") (class "Default")
      (node (ref "LED4") (pin "K") (pinfunction "C_K") (pintype "passive"))
      (node (ref "LED5") (pin "K") (pinfunction "C_K") (pintype "passive"))
      (node (ref "LED6") (pin "K") (pinfunction "C_K") (pintype "passive"))
      (node (ref "LED7") (pin "K") (pinfunction "C_K") (pintype "passive"))
      (node (ref "LED8") (pin "K") (pinfunction "C_K") (pintype "passive"))
      (node (ref "LED9") (pin "K") (pinfunction "C_K") (pintype "passive"))
      (node (ref "R4") (pin "2") (pinfunction "2_2") (pintype "passive"))
    )
    (net (code "44") (name "Net-(Q1-PadB)") (class "Default")
      (node (ref "Q1") (pin "B") (pinfunction "B_B") (pintype "passive"))
      (node (ref "R32") (pin "1") (pinfunction "1_1") (pintype "passive"))
    )
    (net (code "45") (name "Net-(R5-Pad1)") (class "Default")
      (node (ref "R5") (pin "1") (pinfunction "1_1") (pintype "passive"))
      (node (ref "R9") (pin "2") (pinfunction "2_2") (pintype "passive"))
    )
    (net (code "46") (name "Net-(R10-Pad1)") (class "Default")
      (node (ref "R10") (pin "1") (pinfunction "1_1") (pintype "passive"))
      (node (ref "R13") (pin "2") (pinfunction "2_2") (pintype "passive"))
    )
    (net (code "47") (name "Net-(R10-Pad2)") (class "Default")
      (node (ref "R10") (pin "2") (pinfunction "2_2") (pintype "passive"))
      (node (ref "R6") (pin "1") (pinfunction "1_1") (pintype "passive"))
    )
    (net (code "48") (name "Net-(R11-Pad1)") (class "Default")
      (node (ref "R11") (pin "1") (pinfunction "1_1") (pintype "passive"))
      (node (ref "R14") (pin "2") (pinfunction "2_2") (pintype "passive"))
    )
    (net (code "49") (name "Net-(R11-Pad2)") (class "Default")
      (node (ref "R11") (pin "2") (pinfunction "2_2") (pintype "passive"))
      (node (ref "R7") (pin "1") (pinfunction "1_1") (pintype "passive"))
    )
    (net (code "50") (name "Net-(R12-Pad2)") (class "Default")
      (node (ref "R12") (pin "2") (pinfunction "2_2") (pintype "passive"))
      (node (ref "R9") (pin "1") (pinfunction "1_1") (pintype "passive"))
    )
    (net (code "51") (name "Net-(R31-Pad1)") (class "Default")
      (node (ref "R31") (pin "1") (pinfunction "1_1") (pintype "passive"))
      (node (ref "T1") (pin "B") (pinfunction "B_B") (pintype "passive"))
    )
    (net (code "52") (name "Net-(RL1-COIL1)") (class "Default")
      (node (ref "D15") (pin "A") (pinfunction "A_A") (pintype "passive"))
      (node (ref "D16") (pin "A") (pinfunction "A_A") (pintype "passive"))
      (node (ref "D17") (pin "A") (pinfunction "A_A") (pintype "passive"))
      (node (ref "Q1") (pin "C") (pinfunction "C_C") (pintype "passive"))
      (node (ref "RL1") (pin "1") (pinfunction "COIL1_1") (pintype "bidirectional"))
      (node (ref "RL2") (pin "1") (pinfunction "COIL1_1") (pintype "bidirectional"))
      (node (ref "RL3") (pin "1") (pinfunction "COIL1_1") (pintype "bidirectional"))
    )
    (net (code "53") (name "Net-(U1-REF)") (class "Default")
      (node (ref "R29") (pin "1") (pinfunction "1_1") (pintype "passive"))
      (node (ref "R30") (pin "2") (pinfunction "2_2") (pintype "passive"))
      (node (ref "U1") (pin "1") (pinfunction "REF_1") (pintype "input"))
    )
    (net (code "54") (name "Net-(X1A-S)") (class "Default")
      (node (ref "D14") (pin "A") (pinfunction "A_A") (pintype "passive"))
      (node (ref "T1") (pin "C") (pinfunction "C_C") (pintype "passive"))
      (node (ref "X1") (pin "1") (pinfunction "S_1") (pintype "passive"))
    )
    (net (code "55") (name "R") (class "Default")
      (node (ref "R") (pin "TP") (pinfunction "TP_TP") (pintype "input"))
      (node (ref "R5") (pin "2") (pinfunction "2_2") (pintype "passive"))
      (node (ref "TR1") (pin "5") (pinfunction "P2_5") (pintype "passive"))
    )
    (net (code "56") (name "RA") (class "Default")
      (node (ref "CT3") (pin "2") (pinfunction "S1.2_2") (pintype "passive"))
      (node (ref "D8") (pin "A") (pinfunction "A_A") (pintype "passive"))
      (node (ref "R22") (pin "1") (pinfunction "1_1") (pintype "passive"))
      (node (ref "RA") (pin "TP") (pinfunction "TP_TP") (pintype "input"))
      (node (ref "U2") (pin "9") (pinfunction "15/A3_9") (pintype "bidirectional"))
    )
    (net (code "57") (name "RELAY") (class "Default")
      (node (ref "R32") (pin "2") (pinfunction "2_2") (pintype "passive"))
      (node (ref "U2") (pin "16") (pinfunction "TXD2/20_16") (pintype "bidirectional"))
    )
    (net (code "58") (name "RST") (class "Default")
      (node (ref "C16") (pin "2") (pinfunction "2_2") (pintype "passive"))
      (node (ref "R34") (pin "2") (pinfunction "2_2") (pintype "passive"))
      (node (ref "U2") (pin "18") (pinfunction "RST/22_18") (pintype "bidirectional"))
    )
    (net (code "59") (name "RV") (class "Default")
      (node (ref "C1") (pin "2") (pinfunction "2_2") (pintype "passive"))
      (node (ref "R12") (pin "1") (pinfunction "1_1") (pintype "passive"))
      (node (ref "R15") (pin "2") (pinfunction "2_2") (pintype "passive"))
      (node (ref "R16") (pin "1") (pinfunction "1_1") (pintype "passive"))
      (node (ref "RV") (pin "TP") (pinfunction "TP_TP") (pintype "input"))
      (node (ref "U2") (pin "12") (pinfunction "18/A6_12") (pintype "bidirectional"))
    )
    (net (code "60") (name "R_LED") (class "Default")
      (node (ref "LED4") (pin "A") (pinfunction "A_A") (pintype "passive"))
      (node (ref "LED7") (pin "A") (pinfunction "A_A") (pintype "passive"))
      (node (ref "U2") (pin "26") (pinfunction "MOSI/4_26") (pintype "bidirectional"))
    )
    (net (code "61") (name "SCF") (class "Default")
      (node (ref "R23") (pin "2") (pinfunction "2_2") (pintype "passive"))
      (node (ref "R33") (pin "2") (pinfunction "2_2") (pintype "passive"))
      (node (ref "SC") (pin "TP") (pinfunction "TP_TP") (pintype "input"))
      (node (ref "U2") (pin "7") (pinfunction "13/A1_7") (pintype "bidirectional"))
    )
    (net (code "62") (name "STOP") (class "Default")
      (node (ref "SW2") (pin "P$3") (pinfunction "3_P$3") (pintype "passive"))
      (node (ref "SW2") (pin "P$4") (pinfunction "4_P$4") (pintype "passive"))
      (node (ref "U2") (pin "3") (pinfunction "9/RXD1_3") (pintype "bidirectional"))
    )
    (net (code "63") (name "S_LED") (class "Default")
      (node (ref "R2") (pin "1") (pinfunction "1_1") (pintype "passive"))
      (node (ref "U2") (pin "4") (pinfunction "10_4") (pintype "bidirectional"))
    )
    (net (code "64") (name "UPDI") (class "Default")
      (node (ref "J1") (pin "1") (pinfunction "1_1") (pintype "passive"))
      (node (ref "U2") (pin "19") (pinfunction "UPDI_19") (pintype "bidirectional"))
    )
    (net (code "65") (name "VCC") (class "Default")
      (node (ref "C14") (pin "2") (pinfunction "2_2") (pintype "passive"))
      (node (ref "C15") (pin "2") (pinfunction "2_2") (pintype "passive"))
      (node (ref "C19") (pin "+") (pinfunction "+_+") (pintype "passive"))
      (node (ref "C22") (pin "+") (pinfunction "+_+") (pintype "passive"))
      (node (ref "D9") (pin "C") (pinfunction "C_C") (pintype "passive"))
      (node (ref "J1") (pin "2") (pinfunction "2_2") (pintype "passive"))
      (node (ref "R34") (pin "1") (pinfunction "1_1") (pintype "passive"))
      (node (ref "U2") (pin "14") (pinfunction "AVDD_14") (pintype "power_in"))
      (node (ref "U2") (pin "20") (pinfunction "VDD_20") (pintype "power_in"))
      (node (ref "VCC-MC") (pin "TP") (pinfunction "TP_TP") (pintype "input"))
    )
    (net (code "66") (name "VCC1") (class "Default")
      (node (ref "C10") (pin "+") (pinfunction "+_+") (pintype "passive"))
      (node (ref "C11") (pin "+") (pinfunction "+_+") (pintype "passive"))
      (node (ref "C12") (pin "2") (pinfunction "2_2") (pintype "passive"))
      (node (ref "C13") (pin "2") (pinfunction "2_2") (pintype "passive"))
      (node (ref "D2") (pin "C") (pinfunction "C_C") (pintype "passive"))
      (node (ref "IC2") (pin "10") (pinfunction "VDD_10") (pintype "power_in"))
      (node (ref "IC3") (pin "10") (pinfunction "VDD_10") (pintype "power_in"))
      (node (ref "R24") (pin "2") (pinfunction "2_2") (pintype "passive"))
      (node (ref "R25") (pin "2") (pinfunction "2_2") (pintype "passive"))
      (node (ref "R26") (pin "2") (pinfunction "2_2") (pintype "passive"))
      (node (ref "R27") (pin "2") (pinfunction "2_2") (pintype "passive"))
    )
    (net (code "67") (name "VEE") (class "Default")
      (node (ref "B1") (pin "+") (pinfunction "+_+") (pintype "passive"))
      (node (ref "C4") (pin "+") (pinfunction "+_+") (pintype "passive"))
      (node (ref "C5") (pin "+") (pinfunction "+_+") (pintype "passive"))
      (node (ref "C6") (pin "+") (pinfunction "+_+") (pintype "passive"))
      (node (ref "D14") (pin "C") (pinfunction "C_C") (pintype "passive"))
      (node (ref "D15") (pin "C") (pinfunction "C_C") (pintype "passive"))
      (node (ref "D16") (pin "C") (pinfunction "C_C") (pintype "passive"))
      (node (ref "D17") (pin "C") (pinfunction "C_C") (pintype "passive"))
      (node (ref "IC1") (pin "IN") (pinfunction "IN_IN") (pintype "input"))
      (node (ref "R28") (pin "1") (pinfunction "1_1") (pintype "passive"))
      (node (ref "RL1") (pin "2") (pinfunction "COIL2_2") (pintype "bidirectional"))
      (node (ref "RL2") (pin "2") (pinfunction "COIL2_2") (pintype "bidirectional"))
      (node (ref "RL3") (pin "2") (pinfunction "COIL2_2") (pintype "bidirectional"))
      (node (ref "X1") (pin "2") (pinfunction "S_2") (pintype "passive"))
    )
    (net (code "68") (name "V_DIS") (class "Default")
      (node (ref "IC2") (pin "3") (pinfunction "SDA_3") (pintype "input"))
      (node (ref "R24") (pin "1") (pinfunction "1_1") (pintype "passive"))
      (node (ref "U2") (pin "24") (pinfunction "SDA/2_24") (pintype "bidirectional"))
    )
    (net (code "69") (name "V_SCK") (class "Default")
      (node (ref "IC2") (pin "2") (pinfunction "SCL_2") (pintype "input"))
      (node (ref "R26") (pin "1") (pinfunction "1_1") (pintype "passive"))
      (node (ref "U2") (pin "25") (pinfunction "SCL/3_25") (pintype "bidirectional"))
    )
    (net (code "70") (name "Y") (class "Default")
      (node (ref "R6") (pin "2") (pinfunction "2_2") (pintype "passive"))
      (node (ref "Y") (pin "TP") (pinfunction "TP_TP") (pintype "input"))
    )
    (net (code "71") (name "YA") (class "Default")
      (node (ref "CT2") (pin "2") (pinfunction "S1.2_2") (pintype "passive"))
      (node (ref "D3") (pin "A") (pinfunction "A_A") (pintype "passive"))
      (node (ref "R21") (pin "1") (pinfunction "1_1") (pintype "passive"))
      (node (ref "U2") (pin "8") (pinfunction "14/A2_8") (pintype "bidirectional"))
      (node (ref "YA") (pin "TP") (pinfunction "TP_TP") (pintype "input"))
    )
    (net (code "72") (name "YV") (class "Default")
      (node (ref "C2") (pin "2") (pinfunction "2_2") (pintype "passive"))
      (node (ref "R13") (pin "1") (pinfunction "1_1") (pintype "passive"))
      (node (ref "R17") (pin "1") (pinfunction "1_1") (pintype "passive"))
      (node (ref "R18") (pin "1") (pinfunction "1_1") (pintype "passive"))
      (node (ref "U2") (pin "11") (pinfunction "17/A5_11") (pintype "bidirectional"))
      (node (ref "YV") (pin "TP") (pinfunction "TP_TP") (pintype "input"))
    )
    (net (code "73") (name "Y_LED") (class "Default")
      (node (ref "LED5") (pin "A") (pinfunction "A_A") (pintype "passive"))
      (node (ref "LED8") (pin "A") (pinfunction "A_A") (pintype "passive"))
      (node (ref "U2") (pin "27") (pinfunction "MISO/5_27") (pintype "bidirectional"))
    )
    (net (code "74") (name "unconnected-(IC2-DIG4-Pad7)") (class "Default")
      (node (ref "IC2") (pin "7") (pinfunction "DIG4_7") (pintype "bidirectional"))
    )
    (net (code "75") (name "unconnected-(IC3-DIG4-Pad7)") (class "Default")
      (node (ref "IC3") (pin "7") (pinfunction "DIG4_7") (pintype "bidirectional"))
    )
  )
)
